# 7-BOARD_EDGE_FINGERS.net
KiCad netlist of a schematic drawn in Altium Designer
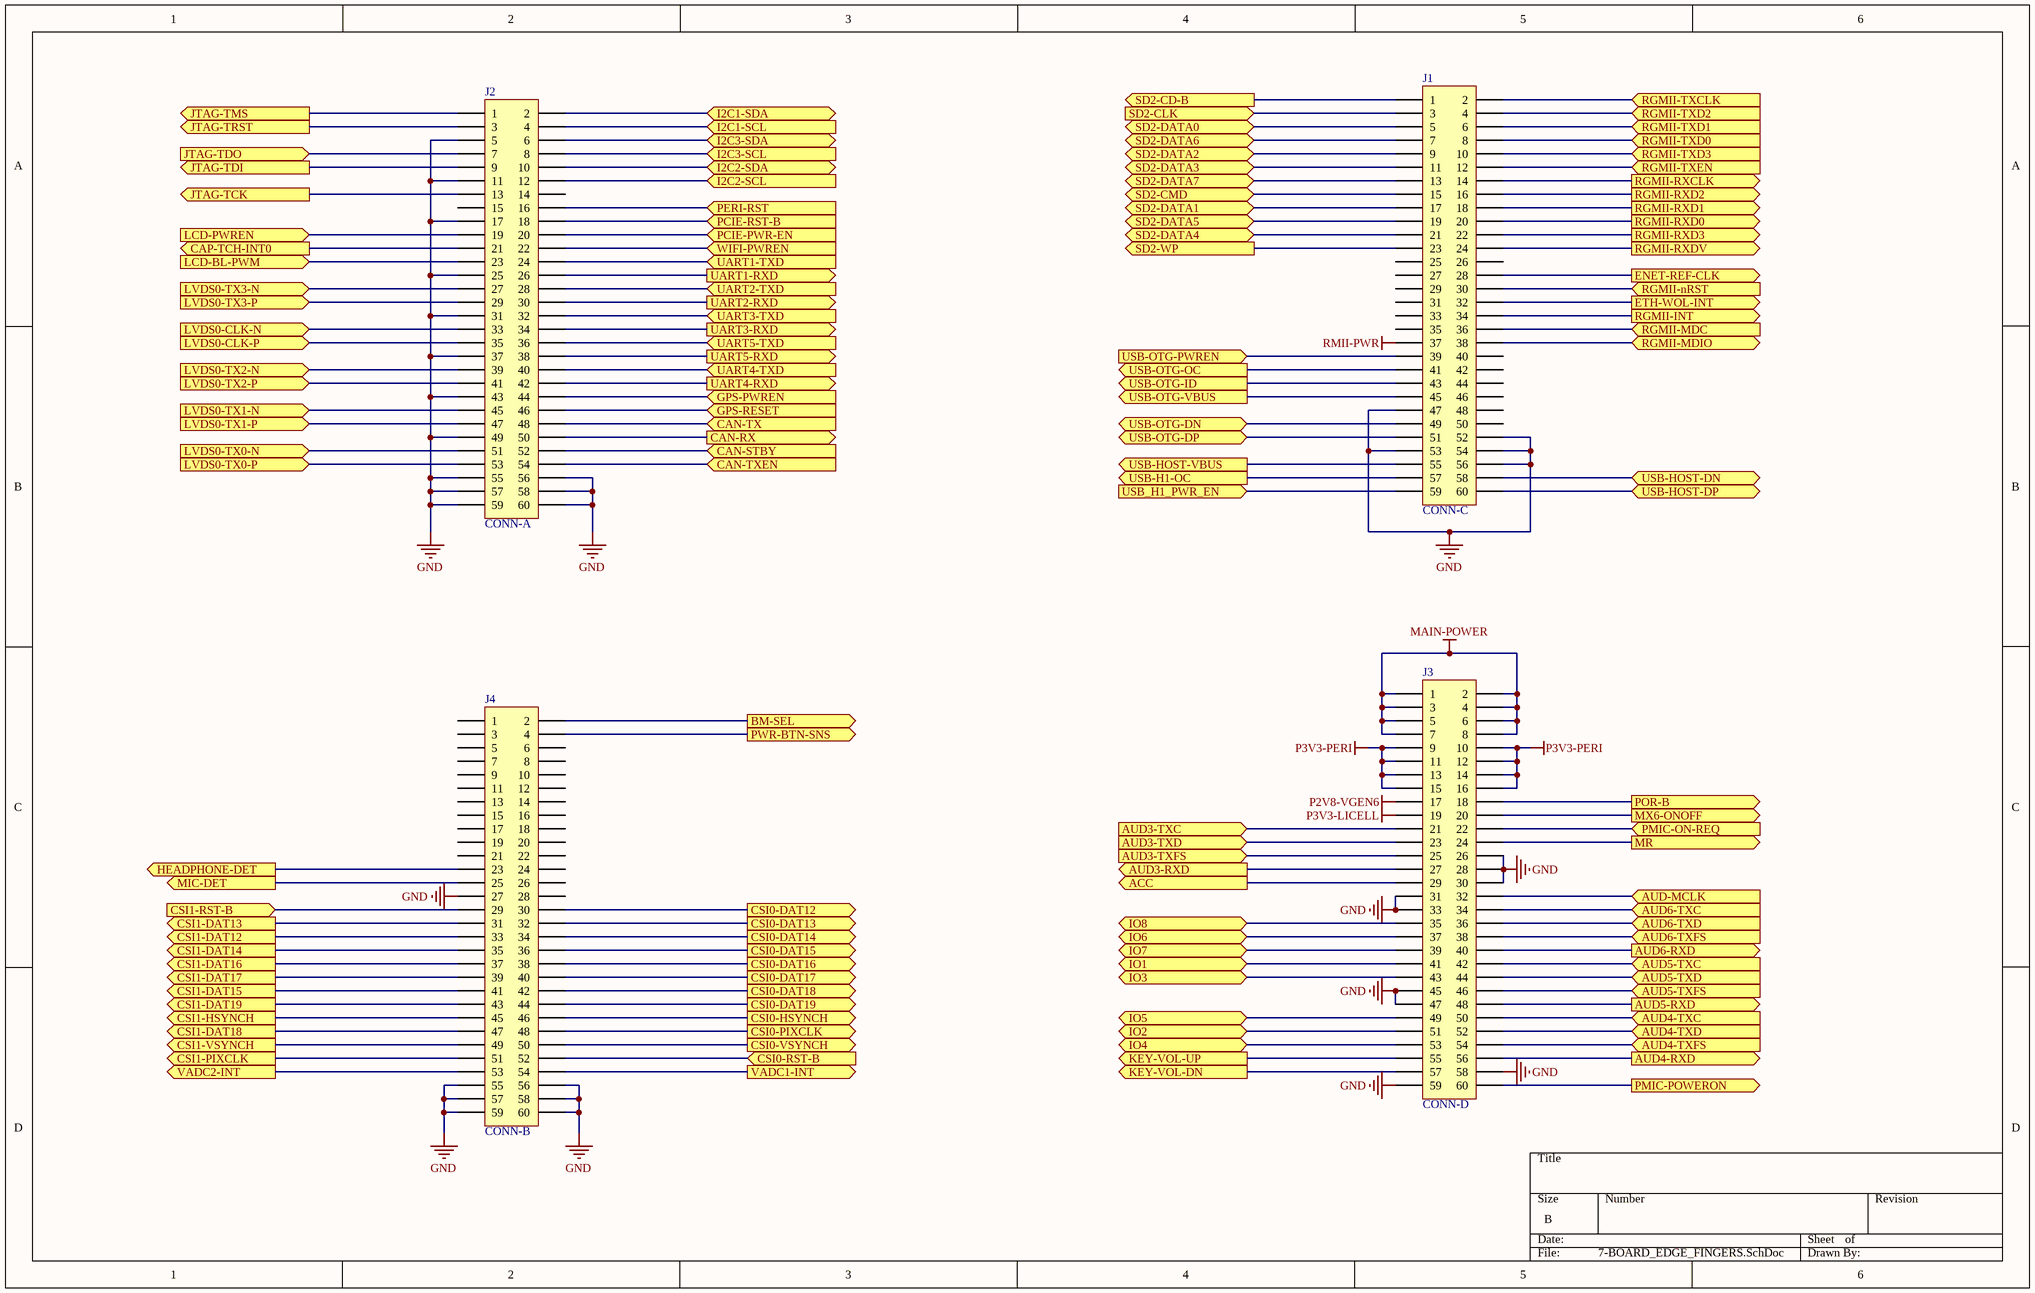
[diagram p0: 7-BOARD_EDGE_FINGERS.SchDoc]

(export (version "E")
  (design (tool "Eeschema 10.0.6"))
  (components
    (comp (ref "J1")
      (value "CONN-C")
      (footprint "BTB0.5-M-60P")
      (description "Header, 30-Pin, Dual row")
      (fields (field (name "PUBLISHER") "Altium Limited"))
      (libsource (lib "Miscellaneous Connectors") (part "Header 30X2"))
    )
    (comp (ref "J2")
      (value "CONN-A")
      (footprint "BTB0.5-M-60P")
      (description "Header, 30-Pin, Dual row")
      (fields (field (name "PUBLISHER") "Altium Limited"))
      (libsource (lib "Miscellaneous Connectors") (part "Header 30X2"))
    )
    (comp (ref "J3")
      (value "CONN-D")
      (footprint "BTB0.5-M-60P")
      (description "Header, 30-Pin, Dual row")
      (fields (field (name "PUBLISHER") "Altium Limited"))
      (libsource (lib "Miscellaneous Connectors") (part "Header 30X2"))
    )
    (comp (ref "J4")
      (value "CONN-B")
      (footprint "BTB0.5-M-60P")
      (description "Header, 30-Pin, Dual row")
      (fields (field (name "PUBLISHER") "Altium Limited"))
      (libsource (lib "Miscellaneous Connectors") (part "Header 30X2"))
    )
  )
  (nets
    (net (code "1") (name "/ACC") (class "Default")
      (node (ref "J3") (pin "29") (pinfunction "29_29") (pintype "passive"))
    )
    (net (code "2") (name "/AUD-MCLK") (class "Default")
      (node (ref "J3") (pin "32") (pinfunction "32_32") (pintype "passive"))
    )
    (net (code "3") (name "/AUD3-RXD") (class "Default")
      (node (ref "J3") (pin "27") (pinfunction "27_27") (pintype "passive"))
    )
    (net (code "4") (name "/AUD3-TXC") (class "Default")
      (node (ref "J3") (pin "21") (pinfunction "21_21") (pintype "passive"))
    )
    (net (code "5") (name "/AUD3-TXD") (class "Default")
      (node (ref "J3") (pin "23") (pinfunction "23_23") (pintype "passive"))
    )
    (net (code "6") (name "/AUD3-TXFS") (class "Default")
      (node (ref "J3") (pin "25") (pinfunction "25_25") (pintype "passive"))
    )
    (net (code "7") (name "/AUD4-RXD") (class "Default")
      (node (ref "J3") (pin "56") (pinfunction "56_56") (pintype "passive"))
    )
    (net (code "8") (name "/AUD4-TXC") (class "Default")
      (node (ref "J3") (pin "50") (pinfunction "50_50") (pintype "passive"))
    )
    (net (code "9") (name "/AUD4-TXD") (class "Default")
      (node (ref "J3") (pin "52") (pinfunction "52_52") (pintype "passive"))
    )
    (net (code "10") (name "/AUD4-TXFS") (class "Default")
      (node (ref "J3") (pin "54") (pinfunction "54_54") (pintype "passive"))
    )
    (net (code "11") (name "/AUD5-RXD") (class "Default")
      (node (ref "J3") (pin "48") (pinfunction "48_48") (pintype "passive"))
    )
    (net (code "12") (name "/AUD5-TXC") (class "Default")
      (node (ref "J3") (pin "42") (pinfunction "42_42") (pintype "passive"))
    )
    (net (code "13") (name "/AUD5-TXD") (class "Default")
      (node (ref "J3") (pin "44") (pinfunction "44_44") (pintype "passive"))
    )
    (net (code "14") (name "/AUD5-TXFS") (class "Default")
      (node (ref "J3") (pin "46") (pinfunction "46_46") (pintype "passive"))
    )
    (net (code "15") (name "/AUD6-RXD") (class "Default")
      (node (ref "J3") (pin "40") (pinfunction "40_40") (pintype "passive"))
    )
    (net (code "16") (name "/AUD6-TXC") (class "Default")
      (node (ref "J3") (pin "34") (pinfunction "34_34") (pintype "passive"))
    )
    (net (code "17") (name "/AUD6-TXD") (class "Default")
      (node (ref "J3") (pin "36") (pinfunction "36_36") (pintype "passive"))
    )
    (net (code "18") (name "/AUD6-TXFS") (class "Default")
      (node (ref "J3") (pin "38") (pinfunction "38_38") (pintype "passive"))
    )
    (net (code "19") (name "/BM-SEL") (class "Default")
      (node (ref "J4") (pin "2") (pinfunction "2_2") (pintype "passive"))
    )
    (net (code "20") (name "/CAN-RX") (class "Default")
      (node (ref "J2") (pin "50") (pinfunction "50_50") (pintype "passive"))
    )
    (net (code "21") (name "/CAN-STBY") (class "Default")
      (node (ref "J2") (pin "52") (pinfunction "52_52") (pintype "passive"))
    )
    (net (code "22") (name "/CAN-TX") (class "Default")
      (node (ref "J2") (pin "48") (pinfunction "48_48") (pintype "passive"))
    )
    (net (code "23") (name "/CAN-TXEN") (class "Default")
      (node (ref "J2") (pin "54") (pinfunction "54_54") (pintype "passive"))
    )
    (net (code "24") (name "/CAP-TCH-INT0") (class "Default")
      (node (ref "J2") (pin "21") (pinfunction "21_21") (pintype "passive"))
    )
    (net (code "25") (name "/CSI0-DAT12") (class "Default")
      (node (ref "J4") (pin "30") (pinfunction "30_30") (pintype "passive"))
    )
    (net (code "26") (name "/CSI0-DAT13") (class "Default")
      (node (ref "J4") (pin "32") (pinfunction "32_32") (pintype "passive"))
    )
    (net (code "27") (name "/CSI0-DAT14") (class "Default")
      (node (ref "J4") (pin "34") (pinfunction "34_34") (pintype "passive"))
    )
    (net (code "28") (name "/CSI0-DAT15") (class "Default")
      (node (ref "J4") (pin "36") (pinfunction "36_36") (pintype "passive"))
    )
    (net (code "29") (name "/CSI0-DAT16") (class "Default")
      (node (ref "J4") (pin "38") (pinfunction "38_38") (pintype "passive"))
    )
    (net (code "30") (name "/CSI0-DAT17") (class "Default")
      (node (ref "J4") (pin "40") (pinfunction "40_40") (pintype "passive"))
    )
    (net (code "31") (name "/CSI0-DAT18") (class "Default")
      (node (ref "J4") (pin "42") (pinfunction "42_42") (pintype "passive"))
    )
    (net (code "32") (name "/CSI0-DAT19") (class "Default")
      (node (ref "J4") (pin "44") (pinfunction "44_44") (pintype "passive"))
    )
    (net (code "33") (name "/CSI0-HSYNCH") (class "Default")
      (node (ref "J4") (pin "46") (pinfunction "46_46") (pintype "passive"))
    )
    (net (code "34") (name "/CSI0-PIXCLK") (class "Default")
      (node (ref "J4") (pin "48") (pinfunction "48_48") (pintype "passive"))
    )
    (net (code "35") (name "/CSI0-RST-B") (class "Default")
      (node (ref "J4") (pin "52") (pinfunction "52_52") (pintype "passive"))
    )
    (net (code "36") (name "/CSI0-VSYNCH") (class "Default")
      (node (ref "J4") (pin "50") (pinfunction "50_50") (pintype "passive"))
    )
    (net (code "37") (name "/CSI1-DAT12") (class "Default")
      (node (ref "J4") (pin "33") (pinfunction "33_33") (pintype "passive"))
    )
    (net (code "38") (name "/CSI1-DAT13") (class "Default")
      (node (ref "J4") (pin "31") (pinfunction "31_31") (pintype "passive"))
    )
    (net (code "39") (name "/CSI1-DAT14") (class "Default")
      (node (ref "J4") (pin "35") (pinfunction "35_35") (pintype "passive"))
    )
    (net (code "40") (name "/CSI1-DAT15") (class "Default")
      (node (ref "J4") (pin "41") (pinfunction "41_41") (pintype "passive"))
    )
    (net (code "41") (name "/CSI1-DAT16") (class "Default")
      (node (ref "J4") (pin "37") (pinfunction "37_37") (pintype "passive"))
    )
    (net (code "42") (name "/CSI1-DAT17") (class "Default")
      (node (ref "J4") (pin "39") (pinfunction "39_39") (pintype "passive"))
    )
    (net (code "43") (name "/CSI1-DAT18") (class "Default")
      (node (ref "J4") (pin "47") (pinfunction "47_47") (pintype "passive"))
    )
    (net (code "44") (name "/CSI1-DAT19") (class "Default")
      (node (ref "J4") (pin "43") (pinfunction "43_43") (pintype "passive"))
    )
    (net (code "45") (name "/CSI1-HSYNCH") (class "Default")
      (node (ref "J4") (pin "45") (pinfunction "45_45") (pintype "passive"))
    )
    (net (code "46") (name "/CSI1-PIXCLK") (class "Default")
      (node (ref "J4") (pin "51") (pinfunction "51_51") (pintype "passive"))
    )
    (net (code "47") (name "/CSI1-RST-B") (class "Default")
      (node (ref "J4") (pin "29") (pinfunction "29_29") (pintype "passive"))
    )
    (net (code "48") (name "/CSI1-VSYNCH") (class "Default")
      (node (ref "J4") (pin "49") (pinfunction "49_49") (pintype "passive"))
    )
    (net (code "49") (name "/ENET-REF-CLK") (class "Default")
      (node (ref "J1") (pin "28") (pinfunction "28_28") (pintype "passive"))
    )
    (net (code "50") (name "/ETH-WOL-INT") (class "Default")
      (node (ref "J1") (pin "32") (pinfunction "32_32") (pintype "passive"))
    )
    (net (code "51") (name "/GPS-PWREN") (class "Default")
      (node (ref "J2") (pin "44") (pinfunction "44_44") (pintype "passive"))
    )
    (net (code "52") (name "/GPS-RESET") (class "Default")
      (node (ref "J2") (pin "46") (pinfunction "46_46") (pintype "passive"))
    )
    (net (code "53") (name "/HEADPHONE-DET") (class "Default")
      (node (ref "J4") (pin "23") (pinfunction "23_23") (pintype "passive"))
    )
    (net (code "54") (name "/I2C1-SCL") (class "Default")
      (node (ref "J2") (pin "4") (pinfunction "4_4") (pintype "passive"))
    )
    (net (code "55") (name "/I2C1-SDA") (class "Default")
      (node (ref "J2") (pin "2") (pinfunction "2_2") (pintype "passive"))
    )
    (net (code "56") (name "/I2C2-SCL") (class "Default")
      (node (ref "J2") (pin "12") (pinfunction "12_12") (pintype "passive"))
    )
    (net (code "57") (name "/I2C2-SDA") (class "Default")
      (node (ref "J2") (pin "10") (pinfunction "10_10") (pintype "passive"))
    )
    (net (code "58") (name "/I2C3-SCL") (class "Default")
      (node (ref "J2") (pin "8") (pinfunction "8_8") (pintype "passive"))
    )
    (net (code "59") (name "/I2C3-SDA") (class "Default")
      (node (ref "J2") (pin "6") (pinfunction "6_6") (pintype "passive"))
    )
    (net (code "60") (name "/IO1") (class "Default")
      (node (ref "J3") (pin "41") (pinfunction "41_41") (pintype "passive"))
    )
    (net (code "61") (name "/IO2") (class "Default")
      (node (ref "J3") (pin "51") (pinfunction "51_51") (pintype "passive"))
    )
    (net (code "62") (name "/IO3") (class "Default")
      (node (ref "J3") (pin "43") (pinfunction "43_43") (pintype "passive"))
    )
    (net (code "63") (name "/IO4") (class "Default")
      (node (ref "J3") (pin "53") (pinfunction "53_53") (pintype "passive"))
    )
    (net (code "64") (name "/IO5") (class "Default")
      (node (ref "J3") (pin "49") (pinfunction "49_49") (pintype "passive"))
    )
    (net (code "65") (name "/IO6") (class "Default")
      (node (ref "J3") (pin "37") (pinfunction "37_37") (pintype "passive"))
    )
    (net (code "66") (name "/IO7") (class "Default")
      (node (ref "J3") (pin "39") (pinfunction "39_39") (pintype "passive"))
    )
    (net (code "67") (name "/IO8") (class "Default")
      (node (ref "J3") (pin "35") (pinfunction "35_35") (pintype "passive"))
    )
    (net (code "68") (name "/JTAG-TCK") (class "Default")
      (node (ref "J2") (pin "13") (pinfunction "13_13") (pintype "passive"))
    )
    (net (code "69") (name "/JTAG-TDI") (class "Default")
      (node (ref "J2") (pin "9") (pinfunction "9_9") (pintype "passive"))
    )
    (net (code "70") (name "/JTAG-TDO") (class "Default")
      (node (ref "J2") (pin "7") (pinfunction "7_7") (pintype "passive"))
    )
    (net (code "71") (name "/JTAG-TMS") (class "Default")
      (node (ref "J2") (pin "1") (pinfunction "1_1") (pintype "passive"))
    )
    (net (code "72") (name "/JTAG-TRST") (class "Default")
      (node (ref "J2") (pin "3") (pinfunction "3_3") (pintype "passive"))
    )
    (net (code "73") (name "/KEY-VOL-DN") (class "Default")
      (node (ref "J3") (pin "57") (pinfunction "57_57") (pintype "passive"))
    )
    (net (code "74") (name "/KEY-VOL-UP") (class "Default")
      (node (ref "J3") (pin "55") (pinfunction "55_55") (pintype "passive"))
    )
    (net (code "75") (name "/LCD-BL-PWM") (class "Default")
      (node (ref "J2") (pin "23") (pinfunction "23_23") (pintype "passive"))
    )
    (net (code "76") (name "/LCD-PWREN") (class "Default")
      (node (ref "J2") (pin "19") (pinfunction "19_19") (pintype "passive"))
    )
    (net (code "77") (name "/LVDS0-CLK-N") (class "Default")
      (node (ref "J2") (pin "33") (pinfunction "33_33") (pintype "passive"))
    )
    (net (code "78") (name "/LVDS0-CLK-P") (class "Default")
      (node (ref "J2") (pin "35") (pinfunction "35_35") (pintype "passive"))
    )
    (net (code "79") (name "/LVDS0-TX0-N") (class "Default")
      (node (ref "J2") (pin "51") (pinfunction "51_51") (pintype "passive"))
    )
    (net (code "80") (name "/LVDS0-TX0-P") (class "Default")
      (node (ref "J2") (pin "53") (pinfunction "53_53") (pintype "passive"))
    )
    (net (code "81") (name "/LVDS0-TX1-N") (class "Default")
      (node (ref "J2") (pin "45") (pinfunction "45_45") (pintype "passive"))
    )
    (net (code "82") (name "/LVDS0-TX1-P") (class "Default")
      (node (ref "J2") (pin "47") (pinfunction "47_47") (pintype "passive"))
    )
    (net (code "83") (name "/LVDS0-TX2-N") (class "Default")
      (node (ref "J2") (pin "39") (pinfunction "39_39") (pintype "passive"))
    )
    (net (code "84") (name "/LVDS0-TX2-P") (class "Default")
      (node (ref "J2") (pin "41") (pinfunction "41_41") (pintype "passive"))
    )
    (net (code "85") (name "/LVDS0-TX3-N") (class "Default")
      (node (ref "J2") (pin "27") (pinfunction "27_27") (pintype "passive"))
    )
    (net (code "86") (name "/LVDS0-TX3-P") (class "Default")
      (node (ref "J2") (pin "29") (pinfunction "29_29") (pintype "passive"))
    )
    (net (code "87") (name "/MIC-DET") (class "Default")
      (node (ref "J4") (pin "25") (pinfunction "25_25") (pintype "passive"))
    )
    (net (code "88") (name "/MR") (class "Default")
      (node (ref "J3") (pin "24") (pinfunction "24_24") (pintype "passive"))
    )
    (net (code "89") (name "/MX6-ONOFF") (class "Default")
      (node (ref "J3") (pin "20") (pinfunction "20_20") (pintype "passive"))
    )
    (net (code "90") (name "/PCIE-PWR-EN") (class "Default")
      (node (ref "J2") (pin "20") (pinfunction "20_20") (pintype "passive"))
    )
    (net (code "91") (name "/PCIE-RST-B") (class "Default")
      (node (ref "J2") (pin "18") (pinfunction "18_18") (pintype "passive"))
    )
    (net (code "92") (name "/PERI-RST") (class "Default")
      (node (ref "J2") (pin "16") (pinfunction "16_16") (pintype "passive"))
    )
    (net (code "93") (name "/PMIC-ON-REQ") (class "Default")
      (node (ref "J3") (pin "22") (pinfunction "22_22") (pintype "passive"))
    )
    (net (code "94") (name "/PMIC-POWERON") (class "Default")
      (node (ref "J3") (pin "60") (pinfunction "60_60") (pintype "passive"))
    )
    (net (code "95") (name "/POR-B") (class "Default")
      (node (ref "J3") (pin "18") (pinfunction "18_18") (pintype "passive"))
    )
    (net (code "96") (name "/PWR-BTN-SNS") (class "Default")
      (node (ref "J4") (pin "4") (pinfunction "4_4") (pintype "passive"))
    )
    (net (code "97") (name "/RGMII-INT") (class "Default")
      (node (ref "J1") (pin "34") (pinfunction "34_34") (pintype "passive"))
    )
    (net (code "98") (name "/RGMII-MDC") (class "Default")
      (node (ref "J1") (pin "36") (pinfunction "36_36") (pintype "passive"))
    )
    (net (code "99") (name "/RGMII-MDIO") (class "Default")
      (node (ref "J1") (pin "38") (pinfunction "38_38") (pintype "passive"))
    )
    (net (code "100") (name "/RGMII-RXCLK") (class "Default")
      (node (ref "J1") (pin "14") (pinfunction "14_14") (pintype "passive"))
    )
    (net (code "101") (name "/RGMII-RXD0") (class "Default")
      (node (ref "J1") (pin "20") (pinfunction "20_20") (pintype "passive"))
    )
    (net (code "102") (name "/RGMII-RXD1") (class "Default")
      (node (ref "J1") (pin "18") (pinfunction "18_18") (pintype "passive"))
    )
    (net (code "103") (name "/RGMII-RXD2") (class "Default")
      (node (ref "J1") (pin "16") (pinfunction "16_16") (pintype "passive"))
    )
    (net (code "104") (name "/RGMII-RXD3") (class "Default")
      (node (ref "J1") (pin "22") (pinfunction "22_22") (pintype "passive"))
    )
    (net (code "105") (name "/RGMII-RXDV") (class "Default")
      (node (ref "J1") (pin "24") (pinfunction "24_24") (pintype "passive"))
    )
    (net (code "106") (name "/RGMII-TXCLK") (class "Default")
      (node (ref "J1") (pin "2") (pinfunction "2_2") (pintype "passive"))
    )
    (net (code "107") (name "/RGMII-TXD0") (class "Default")
      (node (ref "J1") (pin "8") (pinfunction "8_8") (pintype "passive"))
    )
    (net (code "108") (name "/RGMII-TXD1") (class "Default")
      (node (ref "J1") (pin "6") (pinfunction "6_6") (pintype "passive"))
    )
    (net (code "109") (name "/RGMII-TXD2") (class "Default")
      (node (ref "J1") (pin "4") (pinfunction "4_4") (pintype "passive"))
    )
    (net (code "110") (name "/RGMII-TXD3") (class "Default")
      (node (ref "J1") (pin "10") (pinfunction "10_10") (pintype "passive"))
    )
    (net (code "111") (name "/RGMII-TXEN") (class "Default")
      (node (ref "J1") (pin "12") (pinfunction "12_12") (pintype "passive"))
    )
    (net (code "112") (name "/RGMII-nRST") (class "Default")
      (node (ref "J1") (pin "30") (pinfunction "30_30") (pintype "passive"))
    )
    (net (code "113") (name "/SD2-CD-B") (class "Default")
      (node (ref "J1") (pin "1") (pinfunction "1_1") (pintype "passive"))
    )
    (net (code "114") (name "/SD2-CLK") (class "Default")
      (node (ref "J1") (pin "3") (pinfunction "3_3") (pintype "passive"))
    )
    (net (code "115") (name "/SD2-CMD") (class "Default")
      (node (ref "J1") (pin "15") (pinfunction "15_15") (pintype "passive"))
    )
    (net (code "116") (name "/SD2-DATA0") (class "Default")
      (node (ref "J1") (pin "5") (pinfunction "5_5") (pintype "passive"))
    )
    (net (code "117") (name "/SD2-DATA1") (class "Default")
      (node (ref "J1") (pin "17") (pinfunction "17_17") (pintype "passive"))
    )
    (net (code "118") (name "/SD2-DATA2") (class "Default")
      (node (ref "J1") (pin "9") (pinfunction "9_9") (pintype "passive"))
    )
    (net (code "119") (name "/SD2-DATA3") (class "Default")
      (node (ref "J1") (pin "11") (pinfunction "11_11") (pintype "passive"))
    )
    (net (code "120") (name "/SD2-DATA4") (class "Default")
      (node (ref "J1") (pin "21") (pinfunction "21_21") (pintype "passive"))
    )
    (net (code "121") (name "/SD2-DATA5") (class "Default")
      (node (ref "J1") (pin "19") (pinfunction "19_19") (pintype "passive"))
    )
    (net (code "122") (name "/SD2-DATA6") (class "Default")
      (node (ref "J1") (pin "7") (pinfunction "7_7") (pintype "passive"))
    )
    (net (code "123") (name "/SD2-DATA7") (class "Default")
      (node (ref "J1") (pin "13") (pinfunction "13_13") (pintype "passive"))
    )
    (net (code "124") (name "/SD2-WP") (class "Default")
      (node (ref "J1") (pin "23") (pinfunction "23_23") (pintype "passive"))
    )
    (net (code "125") (name "/UART1-RXD") (class "Default")
      (node (ref "J2") (pin "26") (pinfunction "26_26") (pintype "passive"))
    )
    (net (code "126") (name "/UART1-TXD") (class "Default")
      (node (ref "J2") (pin "24") (pinfunction "24_24") (pintype "passive"))
    )
    (net (code "127") (name "/UART2-RXD") (class "Default")
      (node (ref "J2") (pin "30") (pinfunction "30_30") (pintype "passive"))
    )
    (net (code "128") (name "/UART2-TXD") (class "Default")
      (node (ref "J2") (pin "28") (pinfunction "28_28") (pintype "passive"))
    )
    (net (code "129") (name "/UART3-RXD") (class "Default")
      (node (ref "J2") (pin "34") (pinfunction "34_34") (pintype "passive"))
    )
    (net (code "130") (name "/UART3-TXD") (class "Default")
      (node (ref "J2") (pin "32") (pinfunction "32_32") (pintype "passive"))
    )
    (net (code "131") (name "/UART4-RXD") (class "Default")
      (node (ref "J2") (pin "42") (pinfunction "42_42") (pintype "passive"))
    )
    (net (code "132") (name "/UART4-TXD") (class "Default")
      (node (ref "J2") (pin "40") (pinfunction "40_40") (pintype "passive"))
    )
    (net (code "133") (name "/UART5-RXD") (class "Default")
      (node (ref "J2") (pin "38") (pinfunction "38_38") (pintype "passive"))
    )
    (net (code "134") (name "/UART5-TXD") (class "Default")
      (node (ref "J2") (pin "36") (pinfunction "36_36") (pintype "passive"))
    )
    (net (code "135") (name "/USB-H1-OC") (class "Default")
      (node (ref "J1") (pin "57") (pinfunction "57_57") (pintype "passive"))
    )
    (net (code "136") (name "/USB-HOST-DN") (class "Default")
      (node (ref "J1") (pin "58") (pinfunction "58_58") (pintype "passive"))
    )
    (net (code "137") (name "/USB-HOST-DP") (class "Default")
      (node (ref "J1") (pin "60") (pinfunction "60_60") (pintype "passive"))
    )
    (net (code "138") (name "/USB-HOST-VBUS") (class "Default")
      (node (ref "J1") (pin "55") (pinfunction "55_55") (pintype "passive"))
    )
    (net (code "139") (name "/USB-OTG-DN") (class "Default")
      (node (ref "J1") (pin "49") (pinfunction "49_49") (pintype "passive"))
    )
    (net (code "140") (name "/USB-OTG-DP") (class "Default")
      (node (ref "J1") (pin "51") (pinfunction "51_51") (pintype "passive"))
    )
    (net (code "141") (name "/USB-OTG-ID") (class "Default")
      (node (ref "J1") (pin "43") (pinfunction "43_43") (pintype "passive"))
    )
    (net (code "142") (name "/USB-OTG-OC") (class "Default")
      (node (ref "J1") (pin "41") (pinfunction "41_41") (pintype "passive"))
    )
    (net (code "143") (name "/USB-OTG-PWREN") (class "Default")
      (node (ref "J1") (pin "39") (pinfunction "39_39") (pintype "passive"))
    )
    (net (code "144") (name "/USB-OTG-VBUS") (class "Default")
      (node (ref "J1") (pin "45") (pinfunction "45_45") (pintype "passive"))
    )
    (net (code "145") (name "/USB_H1_PWR_EN") (class "Default")
      (node (ref "J1") (pin "59") (pinfunction "59_59") (pintype "passive"))
    )
    (net (code "146") (name "/VADC1-INT") (class "Default")
      (node (ref "J4") (pin "54") (pinfunction "54_54") (pintype "passive"))
    )
    (net (code "147") (name "/VADC2-INT") (class "Default")
      (node (ref "J4") (pin "53") (pinfunction "53_53") (pintype "passive"))
    )
    (net (code "148") (name "/WIFI-PWREN") (class "Default")
      (node (ref "J2") (pin "22") (pinfunction "22_22") (pintype "passive"))
    )
    (net (code "149") (name "GND") (class "Default")
      (node (ref "J1") (pin "47") (pinfunction "47_47") (pintype "passive"))
      (node (ref "J1") (pin "52") (pinfunction "52_52") (pintype "passive"))
      (node (ref "J1") (pin "53") (pinfunction "53_53") (pintype "passive"))
      (node (ref "J1") (pin "54") (pinfunction "54_54") (pintype "passive"))
      (node (ref "J1") (pin "56") (pinfunction "56_56") (pintype "passive"))
      (node (ref "J2") (pin "11") (pinfunction "11_11") (pintype "passive"))
      (node (ref "J2") (pin "17") (pinfunction "17_17") (pintype "passive"))
      (node (ref "J2") (pin "25") (pinfunction "25_25") (pintype "passive"))
      (node (ref "J2") (pin "31") (pinfunction "31_31") (pintype "passive"))
      (node (ref "J2") (pin "37") (pinfunction "37_37") (pintype "passive"))
      (node (ref "J2") (pin "43") (pinfunction "43_43") (pintype "passive"))
      (node (ref "J2") (pin "49") (pinfunction "49_49") (pintype "passive"))
      (node (ref "J2") (pin "5") (pinfunction "5_5") (pintype "passive"))
      (node (ref "J2") (pin "55") (pinfunction "55_55") (pintype "passive"))
      (node (ref "J2") (pin "56") (pinfunction "56_56") (pintype "passive"))
      (node (ref "J2") (pin "57") (pinfunction "57_57") (pintype "passive"))
      (node (ref "J2") (pin "58") (pinfunction "58_58") (pintype "passive"))
      (node (ref "J2") (pin "59") (pinfunction "59_59") (pintype "passive"))
      (node (ref "J2") (pin "60") (pinfunction "60_60") (pintype "passive"))
      (node (ref "J3") (pin "26") (pinfunction "26_26") (pintype "passive"))
      (node (ref "J3") (pin "28") (pinfunction "28_28") (pintype "passive"))
      (node (ref "J3") (pin "30") (pinfunction "30_30") (pintype "passive"))
      (node (ref "J3") (pin "31") (pinfunction "31_31") (pintype "passive"))
      (node (ref "J3") (pin "33") (pinfunction "33_33") (pintype "passive"))
      (node (ref "J3") (pin "45") (pinfunction "45_45") (pintype "passive"))
      (node (ref "J3") (pin "47") (pinfunction "47_47") (pintype "passive"))
      (node (ref "J3") (pin "58") (pinfunction "58_58") (pintype "passive"))
      (node (ref "J3") (pin "59") (pinfunction "59_59") (pintype "passive"))
      (node (ref "J4") (pin "27") (pinfunction "27_27") (pintype "passive"))
      (node (ref "J4") (pin "55") (pinfunction "55_55") (pintype "passive"))
      (node (ref "J4") (pin "56") (pinfunction "56_56") (pintype "passive"))
      (node (ref "J4") (pin "57") (pinfunction "57_57") (pintype "passive"))
      (node (ref "J4") (pin "58") (pinfunction "58_58") (pintype "passive"))
      (node (ref "J4") (pin "59") (pinfunction "59_59") (pintype "passive"))
      (node (ref "J4") (pin "60") (pinfunction "60_60") (pintype "passive"))
    )
    (net (code "150") (name "MAIN-POWER") (class "Default")
      (node (ref "J3") (pin "1") (pinfunction "1_1") (pintype "passive"))
      (node (ref "J3") (pin "2") (pinfunction "2_2") (pintype "passive"))
      (node (ref "J3") (pin "3") (pinfunction "3_3") (pintype "passive"))
      (node (ref "J3") (pin "4") (pinfunction "4_4") (pintype "passive"))
      (node (ref "J3") (pin "5") (pinfunction "5_5") (pintype "passive"))
      (node (ref "J3") (pin "6") (pinfunction "6_6") (pintype "passive"))
      (node (ref "J3") (pin "7") (pinfunction "7_7") (pintype "passive"))
      (node (ref "J3") (pin "8") (pinfunction "8_8") (pintype "passive"))
    )
    (net (code "151") (name "P2V8-VGEN6") (class "Default")
      (node (ref "J3") (pin "17") (pinfunction "17_17") (pintype "passive"))
    )
    (net (code "152") (name "P3V3-LICELL") (class "Default")
      (node (ref "J3") (pin "19") (pinfunction "19_19") (pintype "passive"))
    )
    (net (code "153") (name "P3V3-PERI") (class "Default")
      (node (ref "J3") (pin "10") (pinfunction "10_10") (pintype "passive"))
      (node (ref "J3") (pin "11") (pinfunction "11_11") (pintype "passive"))
      (node (ref "J3") (pin "12") (pinfunction "12_12") (pintype "passive"))
      (node (ref "J3") (pin "13") (pinfunction "13_13") (pintype "passive"))
      (node (ref "J3") (pin "14") (pinfunction "14_14") (pintype "passive"))
      (node (ref "J3") (pin "15") (pinfunction "15_15") (pintype "passive"))
      (node (ref "J3") (pin "16") (pinfunction "16_16") (pintype "passive"))
      (node (ref "J3") (pin "9") (pinfunction "9_9") (pintype "passive"))
    )
    (net (code "154") (name "RMII-PWR") (class "Default")
      (node (ref "J1") (pin "37") (pinfunction "37_37") (pintype "passive"))
    )
    (net (code "155") (name "unconnected-(J1-Pad25)") (class "Default")
      (node (ref "J1") (pin "25") (pinfunction "25_25") (pintype "passive"))
    )
    (net (code "156") (name "unconnected-(J1-Pad26)") (class "Default")
      (node (ref "J1") (pin "26") (pinfunction "26_26") (pintype "passive"))
    )
    (net (code "157") (name "unconnected-(J1-Pad27)") (class "Default")
      (node (ref "J1") (pin "27") (pinfunction "27_27") (pintype "passive"))
    )
    (net (code "158") (name "unconnected-(J1-Pad29)") (class "Default")
      (node (ref "J1") (pin "29") (pinfunction "29_29") (pintype "passive"))
    )
    (net (code "159") (name "unconnected-(J1-Pad31)") (class "Default")
      (node (ref "J1") (pin "31") (pinfunction "31_31") (pintype "passive"))
    )
    (net (code "160") (name "unconnected-(J1-Pad33)") (class "Default")
      (node (ref "J1") (pin "33") (pinfunction "33_33") (pintype "passive"))
    )
    (net (code "161") (name "unconnected-(J1-Pad35)") (class "Default")
      (node (ref "J1") (pin "35") (pinfunction "35_35") (pintype "passive"))
    )
    (net (code "162") (name "unconnected-(J1-Pad40)") (class "Default")
      (node (ref "J1") (pin "40") (pinfunction "40_40") (pintype "passive"))
    )
    (net (code "163") (name "unconnected-(J1-Pad42)") (class "Default")
      (node (ref "J1") (pin "42") (pinfunction "42_42") (pintype "passive"))
    )
    (net (code "164") (name "unconnected-(J1-Pad44)") (class "Default")
      (node (ref "J1") (pin "44") (pinfunction "44_44") (pintype "passive"))
    )
    (net (code "165") (name "unconnected-(J1-Pad46)") (class "Default")
      (node (ref "J1") (pin "46") (pinfunction "46_46") (pintype "passive"))
    )
    (net (code "166") (name "unconnected-(J1-Pad48)") (class "Default")
      (node (ref "J1") (pin "48") (pinfunction "48_48") (pintype "passive"))
    )
    (net (code "167") (name "unconnected-(J1-Pad50)") (class "Default")
      (node (ref "J1") (pin "50") (pinfunction "50_50") (pintype "passive"))
    )
    (net (code "168") (name "unconnected-(J2-Pad14)") (class "Default")
      (node (ref "J2") (pin "14") (pinfunction "14_14") (pintype "passive"))
    )
    (net (code "169") (name "unconnected-(J2-Pad15)") (class "Default")
      (node (ref "J2") (pin "15") (pinfunction "15_15") (pintype "passive"))
    )
    (net (code "170") (name "unconnected-(J4-Pad1)") (class "Default")
      (node (ref "J4") (pin "1") (pinfunction "1_1") (pintype "passive"))
    )
    (net (code "171") (name "unconnected-(J4-Pad3)") (class "Default")
      (node (ref "J4") (pin "3") (pinfunction "3_3") (pintype "passive"))
    )
    (net (code "172") (name "unconnected-(J4-Pad5)") (class "Default")
      (node (ref "J4") (pin "5") (pinfunction "5_5") (pintype "passive"))
    )
    (net (code "173") (name "unconnected-(J4-Pad6)") (class "Default")
      (node (ref "J4") (pin "6") (pinfunction "6_6") (pintype "passive"))
    )
    (net (code "174") (name "unconnected-(J4-Pad7)") (class "Default")
      (node (ref "J4") (pin "7") (pinfunction "7_7") (pintype "passive"))
    )
    (net (code "175") (name "unconnected-(J4-Pad8)") (class "Default")
      (node (ref "J4") (pin "8") (pinfunction "8_8") (pintype "passive"))
    )
    (net (code "176") (name "unconnected-(J4-Pad9)") (class "Default")
      (node (ref "J4") (pin "9") (pinfunction "9_9") (pintype "passive"))
    )
    (net (code "177") (name "unconnected-(J4-Pad10)") (class "Default")
      (node (ref "J4") (pin "10") (pinfunction "10_10") (pintype "passive"))
    )
    (net (code "178") (name "unconnected-(J4-Pad11)") (class "Default")
      (node (ref "J4") (pin "11") (pinfunction "11_11") (pintype "passive"))
    )
    (net (code "179") (name "unconnected-(J4-Pad12)") (class "Default")
      (node (ref "J4") (pin "12") (pinfunction "12_12") (pintype "passive"))
    )
    (net (code "180") (name "unconnected-(J4-Pad13)") (class "Default")
      (node (ref "J4") (pin "13") (pinfunction "13_13") (pintype "passive"))
    )
    (net (code "181") (name "unconnected-(J4-Pad14)") (class "Default")
      (node (ref "J4") (pin "14") (pinfunction "14_14") (pintype "passive"))
    )
    (net (code "182") (name "unconnected-(J4-Pad15)") (class "Default")
      (node (ref "J4") (pin "15") (pinfunction "15_15") (pintype "passive"))
    )
    (net (code "183") (name "unconnected-(J4-Pad16)") (class "Default")
      (node (ref "J4") (pin "16") (pinfunction "16_16") (pintype "passive"))
    )
    (net (code "184") (name "unconnected-(J4-Pad17)") (class "Default")
      (node (ref "J4") (pin "17") (pinfunction "17_17") (pintype "passive"))
    )
    (net (code "185") (name "unconnected-(J4-Pad18)") (class "Default")
      (node (ref "J4") (pin "18") (pinfunction "18_18") (pintype "passive"))
    )
    (net (code "186") (name "unconnected-(J4-Pad19)") (class "Default")
      (node (ref "J4") (pin "19") (pinfunction "19_19") (pintype "passive"))
    )
    (net (code "187") (name "unconnected-(J4-Pad20)") (class "Default")
      (node (ref "J4") (pin "20") (pinfunction "20_20") (pintype "passive"))
    )
    (net (code "188") (name "unconnected-(J4-Pad21)") (class "Default")
      (node (ref "J4") (pin "21") (pinfunction "21_21") (pintype "passive"))
    )
    (net (code "189") (name "unconnected-(J4-Pad22)") (class "Default")
      (node (ref "J4") (pin "22") (pinfunction "22_22") (pintype "passive"))
    )
    (net (code "190") (name "unconnected-(J4-Pad24)") (class "Default")
      (node (ref "J4") (pin "24") (pinfunction "24_24") (pintype "passive"))
    )
    (net (code "191") (name "unconnected-(J4-Pad26)") (class "Default")
      (node (ref "J4") (pin "26") (pinfunction "26_26") (pintype "passive"))
    )
    (net (code "192") (name "unconnected-(J4-Pad28)") (class "Default")
      (node (ref "J4") (pin "28") (pinfunction "28_28") (pintype "passive"))
    )
  )
)
